# display.net
KiCad netlist of a schematic drawn in EAGLE
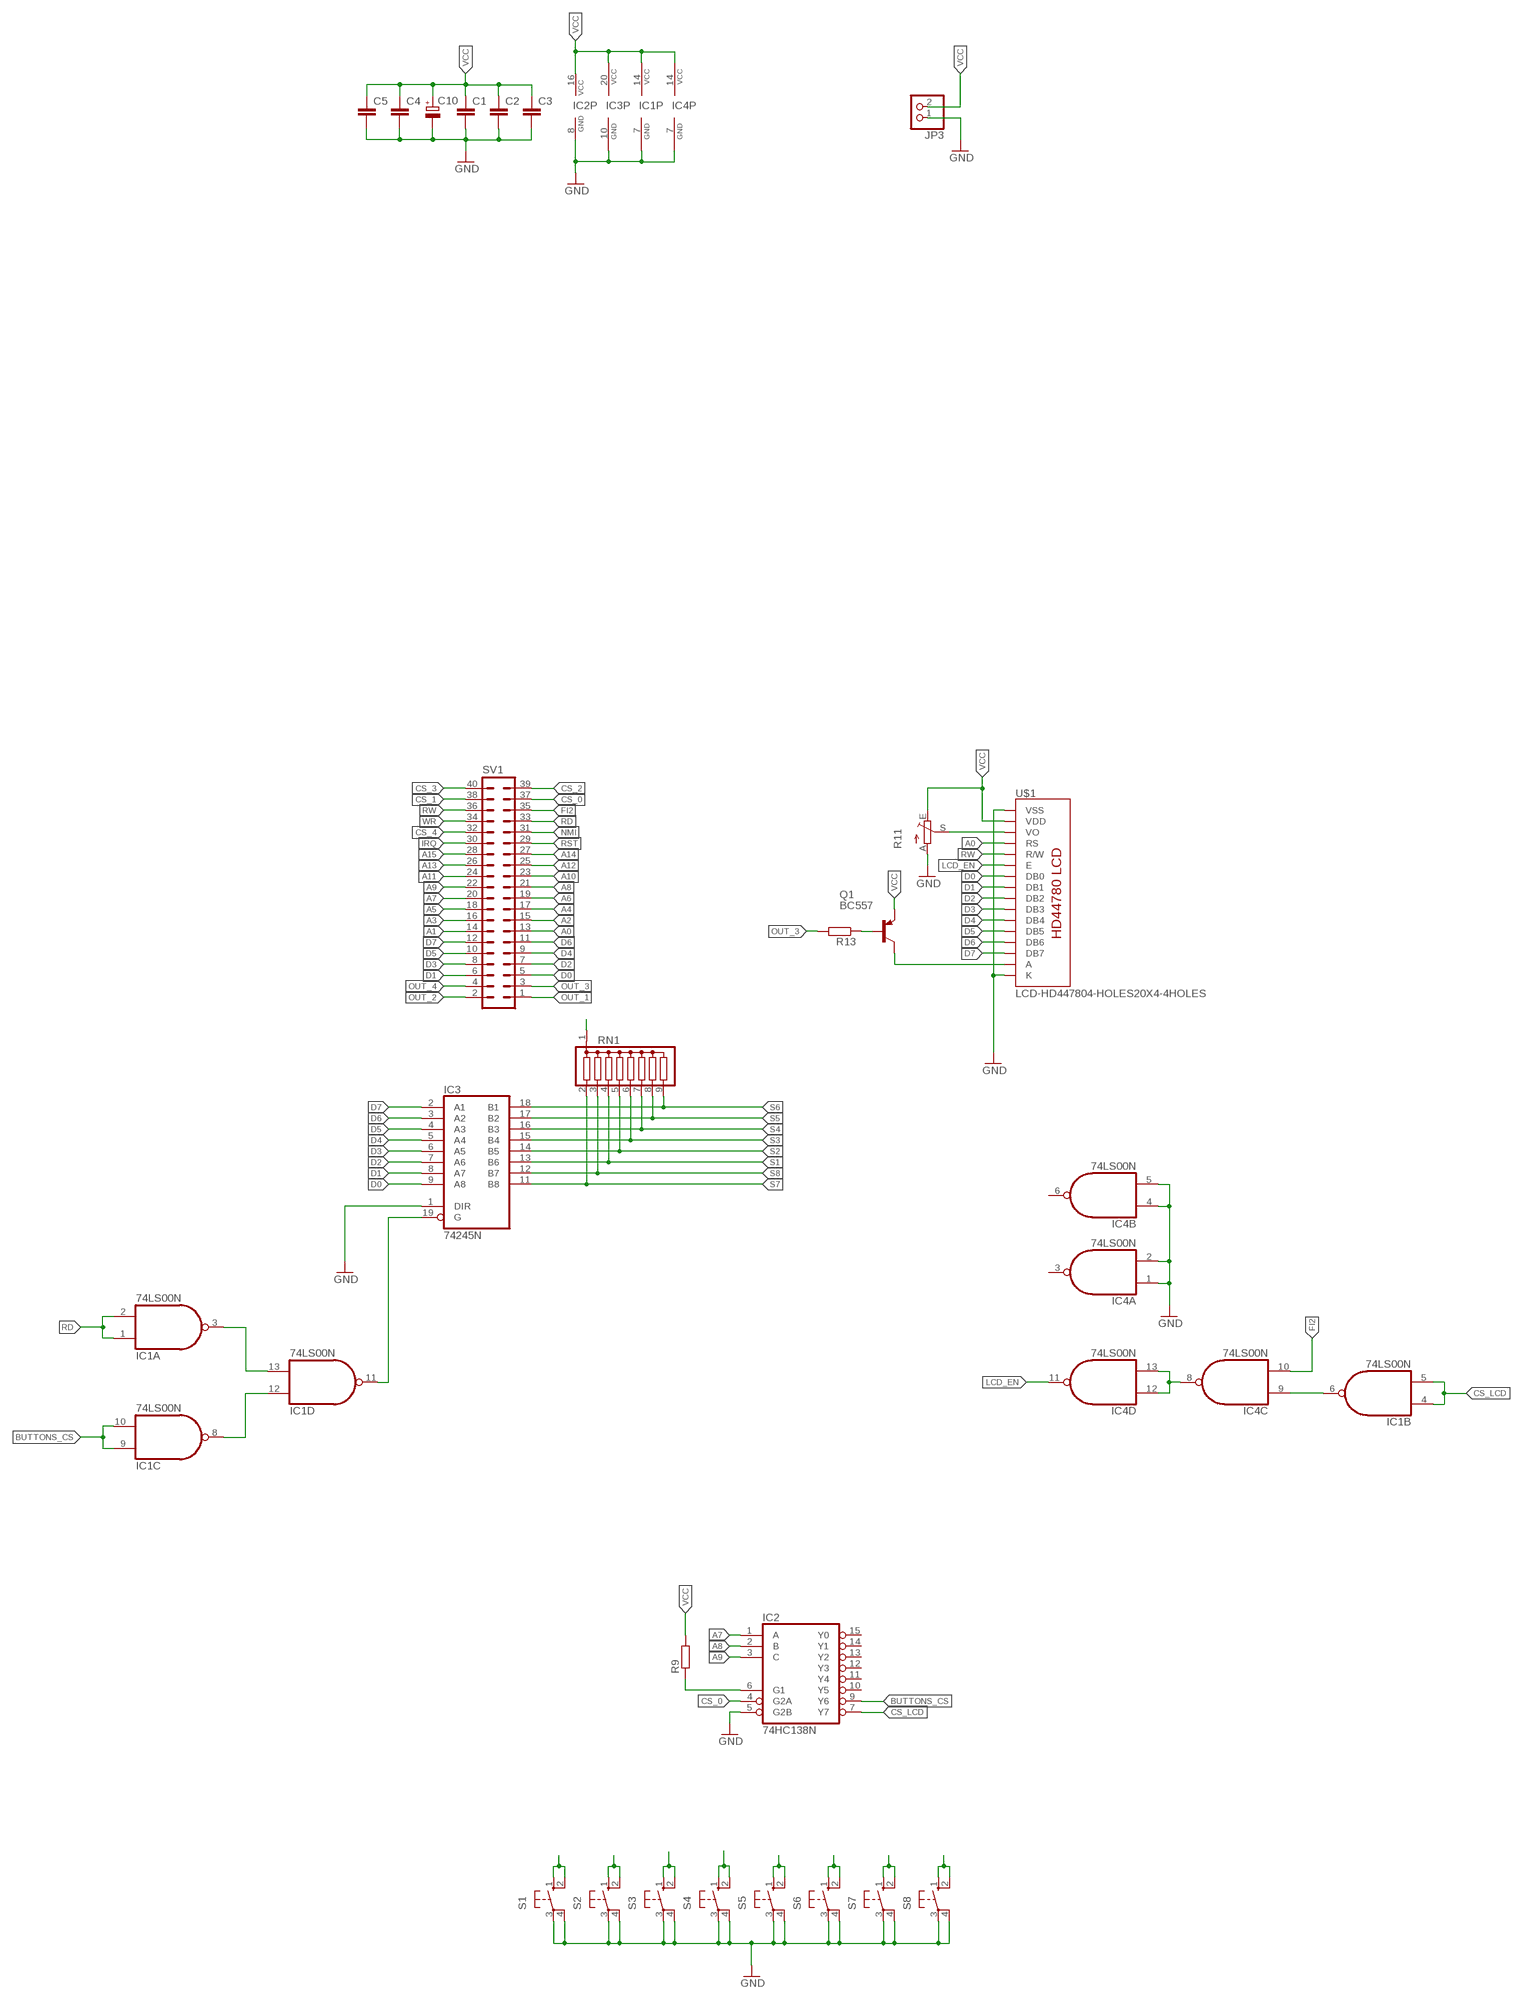
[diagram p0: schematic, sheet 1]

(export (version "E")
  (design (tool "Eeschema 10.0.6"))
  (components
    (comp (ref "C1")
      (value "C-EUC0603")
      (footprint "eagle-import:C0603")
      (libsource (lib "eagle-import") (part "C-EUC0603"))
    )
    (comp (ref "C2")
      (value "C-EUC1206")
      (footprint "eagle-import:C1206")
      (libsource (lib "eagle-import") (part "C-EUC1206"))
    )
    (comp (ref "C3")
      (value "C-EUC1206")
      (footprint "eagle-import:C1206")
      (libsource (lib "eagle-import") (part "C-EUC1206"))
    )
    (comp (ref "C4")
      (value "C-EUC1206")
      (footprint "eagle-import:C1206")
      (libsource (lib "eagle-import") (part "C-EUC1206"))
    )
    (comp (ref "C5")
      (value "C-EUC1206")
      (footprint "eagle-import:C1206")
      (libsource (lib "eagle-import") (part "C-EUC1206"))
    )
    (comp (ref "C10")
      (value "CPOL-EUE5-10.5")
      (footprint "eagle-import:E5-10,5")
      (libsource (lib "eagle-import") (part "CPOL-EUE5-10.5"))
    )
    (comp (ref "IC1")
      (value "74LS00N")
      (footprint "eagle-import:DIL14")
      (libsource (lib "eagle-import") (part "7400NLS"))
    )
    (comp (ref "IC2")
      (value "74HC138N")
      (footprint "eagle-import:DIL16")
      (libsource (lib "eagle-import") (part "74138NHC"))
    )
    (comp (ref "IC3")
      (value "74245N")
      (footprint "eagle-import:DIL20")
      (libsource (lib "eagle-import") (part "74245NLS"))
    )
    (comp (ref "IC4")
      (value "74LS00N")
      (footprint "eagle-import:DIL14")
      (libsource (lib "eagle-import") (part "7400NLS"))
    )
    (comp (ref "JP3")
      (value "PINHD-1X2/90")
      (footprint "eagle-import:1X02_90")
      (libsource (lib "eagle-import") (part "PINHD-1X2/90"))
    )
    (comp (ref "Q1")
      (value "BC557")
      (footprint "eagle-import:TO92")
      (libsource (lib "eagle-import") (part "BC557"))
    )
    (comp (ref "R9")
      (value "R-EU_0204/7")
      (footprint "eagle-import:0204_7")
      (libsource (lib "eagle-import") (part "R-EU_0204/7"))
    )
    (comp (ref "R11")
      (value "TRIM_EU-B25U")
      (footprint "eagle-import:B25U")
      (libsource (lib "eagle-import") (part "TRIM_EU-B25U"))
    )
    (comp (ref "R13")
      (value "R-EU_0204/7")
      (footprint "eagle-import:0204_7")
      (libsource (lib "eagle-import") (part "R-EU_0204/7"))
    )
    (comp (ref "RN1")
      (value "G08R")
      (footprint "eagle-import:SIL9")
      (libsource (lib "eagle-import") (part "G08R"))
    )
    (comp (ref "S1")
      (value "40-XX")
      (footprint "eagle-import:B3F-40XX")
      (fields (field (name "MF") "OMRON COMPONENTS USA") (field (name "MPN") "B3F-4000"))
      (libsource (lib "eagle-import") (part "40-XX"))
    )
    (comp (ref "S2")
      (value "40-XX")
      (footprint "eagle-import:B3F-40XX")
      (fields (field (name "MF") "OMRON COMPONENTS USA") (field (name "MPN") "B3F-4000"))
      (libsource (lib "eagle-import") (part "40-XX"))
    )
    (comp (ref "S3")
      (value "40-XX")
      (footprint "eagle-import:B3F-40XX")
      (fields (field (name "MF") "OMRON COMPONENTS USA") (field (name "MPN") "B3F-4000"))
      (libsource (lib "eagle-import") (part "40-XX"))
    )
    (comp (ref "S4")
      (value "40-XX")
      (footprint "eagle-import:B3F-40XX")
      (fields (field (name "MF") "OMRON COMPONENTS USA") (field (name "MPN") "B3F-4000"))
      (libsource (lib "eagle-import") (part "40-XX"))
    )
    (comp (ref "S5")
      (value "40-XX")
      (footprint "eagle-import:B3F-40XX")
      (fields (field (name "MF") "OMRON COMPONENTS USA") (field (name "MPN") "B3F-4000"))
      (libsource (lib "eagle-import") (part "40-XX"))
    )
    (comp (ref "S6")
      (value "40-XX")
      (footprint "eagle-import:B3F-40XX")
      (fields (field (name "MF") "OMRON COMPONENTS USA") (field (name "MPN") "B3F-4000"))
      (libsource (lib "eagle-import") (part "40-XX"))
    )
    (comp (ref "S7")
      (value "40-XX")
      (footprint "eagle-import:B3F-40XX")
      (fields (field (name "MF") "OMRON COMPONENTS USA") (field (name "MPN") "B3F-4000"))
      (libsource (lib "eagle-import") (part "40-XX"))
    )
    (comp (ref "S8")
      (value "40-XX")
      (footprint "eagle-import:B3F-40XX")
      (fields (field (name "MF") "OMRON COMPONENTS USA") (field (name "MPN") "B3F-4000"))
      (libsource (lib "eagle-import") (part "40-XX"))
    )
    (comp (ref "SV1")
      (value "ML40L")
      (footprint "eagle-import:ML40L")
      (libsource (lib "eagle-import") (part "ML40L"))
    )
    (comp (ref "U$1")
      (value "LCD-HD447804-HOLES20X4-4HOLES")
      (footprint "eagle-import:LCD-20X4-4HOLES")
      (libsource (lib "eagle-import") (part "LCD-HD4478020X4-4HOLES4-HOLES"))
    )
  )
  (nets
    (net (code "1") (name "A0") (class "Default")
      (node (ref "SV1") (pin "13") (pinfunction "13_13") (pintype "passive"))
      (node (ref "U$1") (pin "P$4") (pinfunction "RS_P$4") (pintype "input"))
    )
    (net (code "2") (name "A1") (class "Default")
      (node (ref "SV1") (pin "14") (pinfunction "14_14") (pintype "passive"))
    )
    (net (code "3") (name "A2") (class "Default")
      (node (ref "SV1") (pin "15") (pinfunction "15_15") (pintype "passive"))
    )
    (net (code "4") (name "A3") (class "Default")
      (node (ref "SV1") (pin "16") (pinfunction "16_16") (pintype "passive"))
    )
    (net (code "5") (name "A4") (class "Default")
      (node (ref "SV1") (pin "17") (pinfunction "17_17") (pintype "passive"))
    )
    (net (code "6") (name "A5") (class "Default")
      (node (ref "SV1") (pin "18") (pinfunction "18_18") (pintype "passive"))
    )
    (net (code "7") (name "A6") (class "Default")
      (node (ref "SV1") (pin "19") (pinfunction "19_19") (pintype "passive"))
    )
    (net (code "8") (name "A7") (class "Default")
      (node (ref "IC2") (pin "1") (pinfunction "A_1") (pintype "input"))
      (node (ref "SV1") (pin "20") (pinfunction "20_20") (pintype "passive"))
    )
    (net (code "9") (name "A8") (class "Default")
      (node (ref "IC2") (pin "2") (pinfunction "B_2") (pintype "input"))
      (node (ref "SV1") (pin "21") (pinfunction "21_21") (pintype "passive"))
    )
    (net (code "10") (name "A9") (class "Default")
      (node (ref "IC2") (pin "3") (pinfunction "C_3") (pintype "input"))
      (node (ref "SV1") (pin "22") (pinfunction "22_22") (pintype "passive"))
    )
    (net (code "11") (name "A10") (class "Default")
      (node (ref "SV1") (pin "23") (pinfunction "23_23") (pintype "passive"))
    )
    (net (code "12") (name "A11") (class "Default")
      (node (ref "SV1") (pin "24") (pinfunction "24_24") (pintype "passive"))
    )
    (net (code "13") (name "A12") (class "Default")
      (node (ref "SV1") (pin "25") (pinfunction "25_25") (pintype "passive"))
    )
    (net (code "14") (name "A13") (class "Default")
      (node (ref "SV1") (pin "26") (pinfunction "26_26") (pintype "passive"))
    )
    (net (code "15") (name "A14") (class "Default")
      (node (ref "SV1") (pin "27") (pinfunction "27_27") (pintype "passive"))
    )
    (net (code "16") (name "A15") (class "Default")
      (node (ref "SV1") (pin "28") (pinfunction "28_28") (pintype "passive"))
    )
    (net (code "17") (name "BUTTONS_CS") (class "Default")
      (node (ref "IC1") (pin "10") (pinfunction "I1_10") (pintype "input"))
      (node (ref "IC1") (pin "9") (pinfunction "I0_9") (pintype "input"))
      (node (ref "IC2") (pin "9") (pinfunction "Y6_9") (pintype "output"))
    )
    (net (code "18") (name "CS_0") (class "Default")
      (node (ref "IC2") (pin "4") (pinfunction "G2A_4") (pintype "input"))
      (node (ref "SV1") (pin "37") (pinfunction "37_37") (pintype "passive"))
    )
    (net (code "19") (name "CS_1") (class "Default")
      (node (ref "SV1") (pin "38") (pinfunction "38_38") (pintype "passive"))
    )
    (net (code "20") (name "CS_2") (class "Default")
      (node (ref "SV1") (pin "39") (pinfunction "39_39") (pintype "passive"))
    )
    (net (code "21") (name "CS_3") (class "Default")
      (node (ref "SV1") (pin "40") (pinfunction "40_40") (pintype "passive"))
    )
    (net (code "22") (name "CS_4") (class "Default")
      (node (ref "SV1") (pin "32") (pinfunction "32_32") (pintype "passive"))
    )
    (net (code "23") (name "CS_LCD") (class "Default")
      (node (ref "IC1") (pin "4") (pinfunction "I0_4") (pintype "input"))
      (node (ref "IC1") (pin "5") (pinfunction "I1_5") (pintype "input"))
      (node (ref "IC2") (pin "7") (pinfunction "Y7_7") (pintype "output"))
    )
    (net (code "24") (name "D0") (class "Default")
      (node (ref "IC3") (pin "9") (pinfunction "A8_9") (pintype "bidirectional"))
      (node (ref "SV1") (pin "5") (pinfunction "5_5") (pintype "passive"))
      (node (ref "U$1") (pin "P$7") (pinfunction "DB0_P$7") (pintype "bidirectional"))
    )
    (net (code "25") (name "D1") (class "Default")
      (node (ref "IC3") (pin "8") (pinfunction "A7_8") (pintype "bidirectional"))
      (node (ref "SV1") (pin "6") (pinfunction "6_6") (pintype "passive"))
      (node (ref "U$1") (pin "P$8") (pinfunction "DB1_P$8") (pintype "bidirectional"))
    )
    (net (code "26") (name "D2") (class "Default")
      (node (ref "IC3") (pin "7") (pinfunction "A6_7") (pintype "bidirectional"))
      (node (ref "SV1") (pin "7") (pinfunction "7_7") (pintype "passive"))
      (node (ref "U$1") (pin "P$9") (pinfunction "DB2_P$9") (pintype "bidirectional"))
    )
    (net (code "27") (name "D3") (class "Default")
      (node (ref "IC3") (pin "6") (pinfunction "A5_6") (pintype "bidirectional"))
      (node (ref "SV1") (pin "8") (pinfunction "8_8") (pintype "passive"))
      (node (ref "U$1") (pin "P$10") (pinfunction "DB3_P$10") (pintype "bidirectional"))
    )
    (net (code "28") (name "D4") (class "Default")
      (node (ref "IC3") (pin "5") (pinfunction "A4_5") (pintype "bidirectional"))
      (node (ref "SV1") (pin "9") (pinfunction "9_9") (pintype "passive"))
      (node (ref "U$1") (pin "P$11") (pinfunction "DB4_P$11") (pintype "bidirectional"))
    )
    (net (code "29") (name "D5") (class "Default")
      (node (ref "IC3") (pin "4") (pinfunction "A3_4") (pintype "bidirectional"))
      (node (ref "SV1") (pin "10") (pinfunction "10_10") (pintype "passive"))
      (node (ref "U$1") (pin "P$12") (pinfunction "DB5_P$12") (pintype "bidirectional"))
    )
    (net (code "30") (name "D6") (class "Default")
      (node (ref "IC3") (pin "3") (pinfunction "A2_3") (pintype "bidirectional"))
      (node (ref "SV1") (pin "11") (pinfunction "11_11") (pintype "passive"))
      (node (ref "U$1") (pin "P$13") (pinfunction "DB6_P$13") (pintype "bidirectional"))
    )
    (net (code "31") (name "D7") (class "Default")
      (node (ref "IC3") (pin "2") (pinfunction "A1_2") (pintype "bidirectional"))
      (node (ref "SV1") (pin "12") (pinfunction "12_12") (pintype "passive"))
      (node (ref "U$1") (pin "P$14") (pinfunction "DB7_P$14") (pintype "bidirectional"))
    )
    (net (code "32") (name "FI2") (class "Default")
      (node (ref "IC4") (pin "10") (pinfunction "I1_10") (pintype "input"))
      (node (ref "SV1") (pin "35") (pinfunction "35_35") (pintype "passive"))
    )
    (net (code "33") (name "GND") (class "Default")
      (node (ref "C1") (pin "2") (pinfunction "2_2") (pintype "passive"))
      (node (ref "C10") (pin "-") (pinfunction "-_-") (pintype "passive"))
      (node (ref "C2") (pin "2") (pinfunction "2_2") (pintype "passive"))
      (node (ref "C3") (pin "2") (pinfunction "2_2") (pintype "passive"))
      (node (ref "C4") (pin "2") (pinfunction "2_2") (pintype "passive"))
      (node (ref "C5") (pin "2") (pinfunction "2_2") (pintype "passive"))
      (node (ref "IC1") (pin "7") (pinfunction "GND_7") (pintype "power_in"))
      (node (ref "IC2") (pin "5") (pinfunction "G2B_5") (pintype "input"))
      (node (ref "IC2") (pin "8") (pinfunction "GND_8") (pintype "power_in"))
      (node (ref "IC3") (pin "1") (pinfunction "DIR_1") (pintype "input"))
      (node (ref "IC3") (pin "10") (pinfunction "GND_10") (pintype "power_in"))
      (node (ref "IC4") (pin "1") (pinfunction "I0_1") (pintype "input"))
      (node (ref "IC4") (pin "2") (pinfunction "I1_2") (pintype "input"))
      (node (ref "IC4") (pin "4") (pinfunction "I0_4") (pintype "input"))
      (node (ref "IC4") (pin "5") (pinfunction "I1_5") (pintype "input"))
      (node (ref "IC4") (pin "7") (pinfunction "GND_7") (pintype "power_in"))
      (node (ref "JP3") (pin "1") (pinfunction "1_1") (pintype "passive"))
      (node (ref "R11") (pin "A") (pinfunction "A_A") (pintype "passive"))
      (node (ref "S1") (pin "3") (pinfunction "P_3") (pintype "passive"))
      (node (ref "S1") (pin "4") (pinfunction "P1_4") (pintype "passive"))
      (node (ref "S2") (pin "3") (pinfunction "P_3") (pintype "passive"))
      (node (ref "S2") (pin "4") (pinfunction "P1_4") (pintype "passive"))
      (node (ref "S3") (pin "3") (pinfunction "P_3") (pintype "passive"))
      (node (ref "S3") (pin "4") (pinfunction "P1_4") (pintype "passive"))
      (node (ref "S4") (pin "3") (pinfunction "P_3") (pintype "passive"))
      (node (ref "S4") (pin "4") (pinfunction "P1_4") (pintype "passive"))
      (node (ref "S5") (pin "3") (pinfunction "P_3") (pintype "passive"))
      (node (ref "S5") (pin "4") (pinfunction "P1_4") (pintype "passive"))
      (node (ref "S6") (pin "3") (pinfunction "P_3") (pintype "passive"))
      (node (ref "S6") (pin "4") (pinfunction "P1_4") (pintype "passive"))
      (node (ref "S7") (pin "3") (pinfunction "P_3") (pintype "passive"))
      (node (ref "S7") (pin "4") (pinfunction "P1_4") (pintype "passive"))
      (node (ref "S8") (pin "3") (pinfunction "P_3") (pintype "passive"))
      (node (ref "S8") (pin "4") (pinfunction "P1_4") (pintype "passive"))
      (node (ref "U$1") (pin "P$1") (pinfunction "VSS_P$1") (pintype "power_in"))
      (node (ref "U$1") (pin "P$16") (pinfunction "K_P$16") (pintype "power_in"))
    )
    (net (code "34") (name "IRQ") (class "Default")
      (node (ref "SV1") (pin "30") (pinfunction "30_30") (pintype "passive"))
    )
    (net (code "35") (name "LCD_EN") (class "Default")
      (node (ref "IC4") (pin "11") (pinfunction "O_11") (pintype "output"))
      (node (ref "U$1") (pin "P$6") (pinfunction "E_P$6") (pintype "input"))
    )
    (net (code "36") (name "NMI") (class "Default")
      (node (ref "SV1") (pin "31") (pinfunction "31_31") (pintype "passive"))
    )
    (net (code "37") (name "Net-(IC1A-O)") (class "Default")
      (node (ref "IC1") (pin "13") (pinfunction "I1_13") (pintype "input"))
      (node (ref "IC1") (pin "3") (pinfunction "O_3") (pintype "output"))
    )
    (net (code "38") (name "Net-(IC1B-O)") (class "Default")
      (node (ref "IC1") (pin "6") (pinfunction "O_6") (pintype "output"))
      (node (ref "IC4") (pin "9") (pinfunction "I0_9") (pintype "input"))
    )
    (net (code "39") (name "Net-(IC1C-O)") (class "Default")
      (node (ref "IC1") (pin "12") (pinfunction "I0_12") (pintype "input"))
      (node (ref "IC1") (pin "8") (pinfunction "O_8") (pintype "output"))
    )
    (net (code "40") (name "Net-(IC1D-O)") (class "Default")
      (node (ref "IC1") (pin "11") (pinfunction "O_11") (pintype "output"))
      (node (ref "IC3") (pin "19") (pinfunction "G_19") (pintype "input"))
    )
    (net (code "41") (name "Net-(IC2A-G1)") (class "Default")
      (node (ref "IC2") (pin "6") (pinfunction "G1_6") (pintype "input"))
      (node (ref "R9") (pin "1") (pinfunction "1_1") (pintype "passive"))
    )
    (net (code "42") (name "Net-(IC4C-O)") (class "Default")
      (node (ref "IC4") (pin "12") (pinfunction "I0_12") (pintype "input"))
      (node (ref "IC4") (pin "13") (pinfunction "I1_13") (pintype "input"))
      (node (ref "IC4") (pin "8") (pinfunction "O_8") (pintype "output"))
    )
    (net (code "43") (name "Net-(Q1-B)") (class "Default")
      (node (ref "Q1") (pin "2") (pinfunction "B_2") (pintype "passive"))
      (node (ref "R13") (pin "1") (pinfunction "1_1") (pintype "passive"))
    )
    (net (code "44") (name "Net-(Q1-C)") (class "Default")
      (node (ref "Q1") (pin "3") (pinfunction "C_3") (pintype "passive"))
      (node (ref "U$1") (pin "P$15") (pinfunction "A_P$15") (pintype "power_in"))
    )
    (net (code "45") (name "Net-(U$1-VO)") (class "Default")
      (node (ref "R11") (pin "S") (pinfunction "S_S") (pintype "passive"))
      (node (ref "U$1") (pin "P$3") (pinfunction "VO_P$3") (pintype "bidirectional"))
    )
    (net (code "46") (name "OUT_1") (class "Default")
      (node (ref "SV1") (pin "1") (pinfunction "1_1") (pintype "passive"))
    )
    (net (code "47") (name "OUT_2") (class "Default")
      (node (ref "SV1") (pin "2") (pinfunction "2_2") (pintype "passive"))
    )
    (net (code "48") (name "OUT_3") (class "Default")
      (node (ref "R13") (pin "2") (pinfunction "2_2") (pintype "passive"))
      (node (ref "SV1") (pin "3") (pinfunction "3_3") (pintype "passive"))
    )
    (net (code "49") (name "OUT_4") (class "Default")
      (node (ref "SV1") (pin "4") (pinfunction "4_4") (pintype "passive"))
    )
    (net (code "50") (name "RD") (class "Default")
      (node (ref "IC1") (pin "1") (pinfunction "I0_1") (pintype "input"))
      (node (ref "IC1") (pin "2") (pinfunction "I1_2") (pintype "input"))
      (node (ref "SV1") (pin "33") (pinfunction "33_33") (pintype "passive"))
    )
    (net (code "51") (name "RST") (class "Default")
      (node (ref "SV1") (pin "29") (pinfunction "29_29") (pintype "passive"))
    )
    (net (code "52") (name "RW") (class "Default")
      (node (ref "SV1") (pin "36") (pinfunction "36_36") (pintype "passive"))
      (node (ref "U$1") (pin "P$5") (pinfunction "R/W_P$5") (pintype "input"))
    )
    (net (code "53") (name "S1") (class "Default")
      (node (ref "IC3") (pin "13") (pinfunction "B6_13") (pintype "bidirectional"))
      (node (ref "RN1") (pin "4") (pinfunction "4_4") (pintype "passive"))
      (node (ref "S1") (pin "1") (pinfunction "S_1") (pintype "passive"))
      (node (ref "S1") (pin "2") (pinfunction "S1_2") (pintype "passive"))
    )
    (net (code "54") (name "S2") (class "Default")
      (node (ref "IC3") (pin "14") (pinfunction "B5_14") (pintype "bidirectional"))
      (node (ref "RN1") (pin "5") (pinfunction "5_5") (pintype "passive"))
      (node (ref "S2") (pin "1") (pinfunction "S_1") (pintype "passive"))
      (node (ref "S2") (pin "2") (pinfunction "S1_2") (pintype "passive"))
    )
    (net (code "55") (name "S3") (class "Default")
      (node (ref "IC3") (pin "15") (pinfunction "B4_15") (pintype "bidirectional"))
      (node (ref "RN1") (pin "6") (pinfunction "6_6") (pintype "passive"))
      (node (ref "S3") (pin "1") (pinfunction "S_1") (pintype "passive"))
      (node (ref "S3") (pin "2") (pinfunction "S1_2") (pintype "passive"))
    )
    (net (code "56") (name "S4") (class "Default")
      (node (ref "IC3") (pin "16") (pinfunction "B3_16") (pintype "bidirectional"))
      (node (ref "RN1") (pin "7") (pinfunction "7_7") (pintype "passive"))
      (node (ref "S4") (pin "1") (pinfunction "S_1") (pintype "passive"))
      (node (ref "S4") (pin "2") (pinfunction "S1_2") (pintype "passive"))
    )
    (net (code "57") (name "S5") (class "Default")
      (node (ref "IC3") (pin "17") (pinfunction "B2_17") (pintype "bidirectional"))
      (node (ref "RN1") (pin "8") (pinfunction "8_8") (pintype "passive"))
      (node (ref "S5") (pin "1") (pinfunction "S_1") (pintype "passive"))
      (node (ref "S5") (pin "2") (pinfunction "S1_2") (pintype "passive"))
    )
    (net (code "58") (name "S6") (class "Default")
      (node (ref "IC3") (pin "18") (pinfunction "B1_18") (pintype "bidirectional"))
      (node (ref "RN1") (pin "9") (pinfunction "9_9") (pintype "passive"))
      (node (ref "S6") (pin "1") (pinfunction "S_1") (pintype "passive"))
      (node (ref "S6") (pin "2") (pinfunction "S1_2") (pintype "passive"))
    )
    (net (code "59") (name "S7") (class "Default")
      (node (ref "IC3") (pin "11") (pinfunction "B8_11") (pintype "bidirectional"))
      (node (ref "RN1") (pin "2") (pinfunction "2_2") (pintype "passive"))
      (node (ref "S7") (pin "1") (pinfunction "S_1") (pintype "passive"))
      (node (ref "S7") (pin "2") (pinfunction "S1_2") (pintype "passive"))
    )
    (net (code "60") (name "S8") (class "Default")
      (node (ref "IC3") (pin "12") (pinfunction "B7_12") (pintype "bidirectional"))
      (node (ref "RN1") (pin "3") (pinfunction "3_3") (pintype "passive"))
      (node (ref "S8") (pin "1") (pinfunction "S_1") (pintype "passive"))
      (node (ref "S8") (pin "2") (pinfunction "S1_2") (pintype "passive"))
    )
    (net (code "61") (name "VCC") (class "Default")
      (node (ref "C1") (pin "1") (pinfunction "1_1") (pintype "passive"))
      (node (ref "C10") (pin "+") (pinfunction "+_+") (pintype "passive"))
      (node (ref "C2") (pin "1") (pinfunction "1_1") (pintype "passive"))
      (node (ref "C3") (pin "1") (pinfunction "1_1") (pintype "passive"))
      (node (ref "C4") (pin "1") (pinfunction "1_1") (pintype "passive"))
      (node (ref "C5") (pin "1") (pinfunction "1_1") (pintype "passive"))
      (node (ref "IC1") (pin "14") (pinfunction "VCC_14") (pintype "power_in"))
      (node (ref "IC2") (pin "16") (pinfunction "VCC_16") (pintype "power_in"))
      (node (ref "IC3") (pin "20") (pinfunction "VCC_20") (pintype "power_in"))
      (node (ref "IC4") (pin "14") (pinfunction "VCC_14") (pintype "power_in"))
      (node (ref "JP3") (pin "2") (pinfunction "2_2") (pintype "passive"))
      (node (ref "Q1") (pin "1") (pinfunction "E_1") (pintype "passive"))
      (node (ref "R11") (pin "E") (pinfunction "E_E") (pintype "passive"))
      (node (ref "R9") (pin "2") (pinfunction "2_2") (pintype "passive"))
      (node (ref "RN1") (pin "1") (pinfunction "1_1") (pintype "passive"))
      (node (ref "U$1") (pin "P$2") (pinfunction "VDD_P$2") (pintype "power_in"))
    )
    (net (code "62") (name "WR") (class "Default")
      (node (ref "SV1") (pin "34") (pinfunction "34_34") (pintype "passive"))
    )
    (net (code "63") (name "unconnected-(IC2A-Y0-Pad15)") (class "Default")
      (node (ref "IC2") (pin "15") (pinfunction "Y0_15") (pintype "output"))
    )
    (net (code "64") (name "unconnected-(IC2A-Y1-Pad14)") (class "Default")
      (node (ref "IC2") (pin "14") (pinfunction "Y1_14") (pintype "output"))
    )
    (net (code "65") (name "unconnected-(IC2A-Y2-Pad13)") (class "Default")
      (node (ref "IC2") (pin "13") (pinfunction "Y2_13") (pintype "output"))
    )
    (net (code "66") (name "unconnected-(IC2A-Y3-Pad12)") (class "Default")
      (node (ref "IC2") (pin "12") (pinfunction "Y3_12") (pintype "output"))
    )
    (net (code "67") (name "unconnected-(IC2A-Y4-Pad11)") (class "Default")
      (node (ref "IC2") (pin "11") (pinfunction "Y4_11") (pintype "output"))
    )
    (net (code "68") (name "unconnected-(IC2A-Y5-Pad10)") (class "Default")
      (node (ref "IC2") (pin "10") (pinfunction "Y5_10") (pintype "output"))
    )
    (net (code "69") (name "unconnected-(IC4A-O-Pad3)") (class "Default")
      (node (ref "IC4") (pin "3") (pinfunction "O_3") (pintype "output"))
    )
    (net (code "70") (name "unconnected-(IC4B-O-Pad6)") (class "Default")
      (node (ref "IC4") (pin "6") (pinfunction "O_6") (pintype "output"))
    )
  )
)
